# DM1097_Connector.net
KiCad netlist of a schematic drawn in Altium Designer
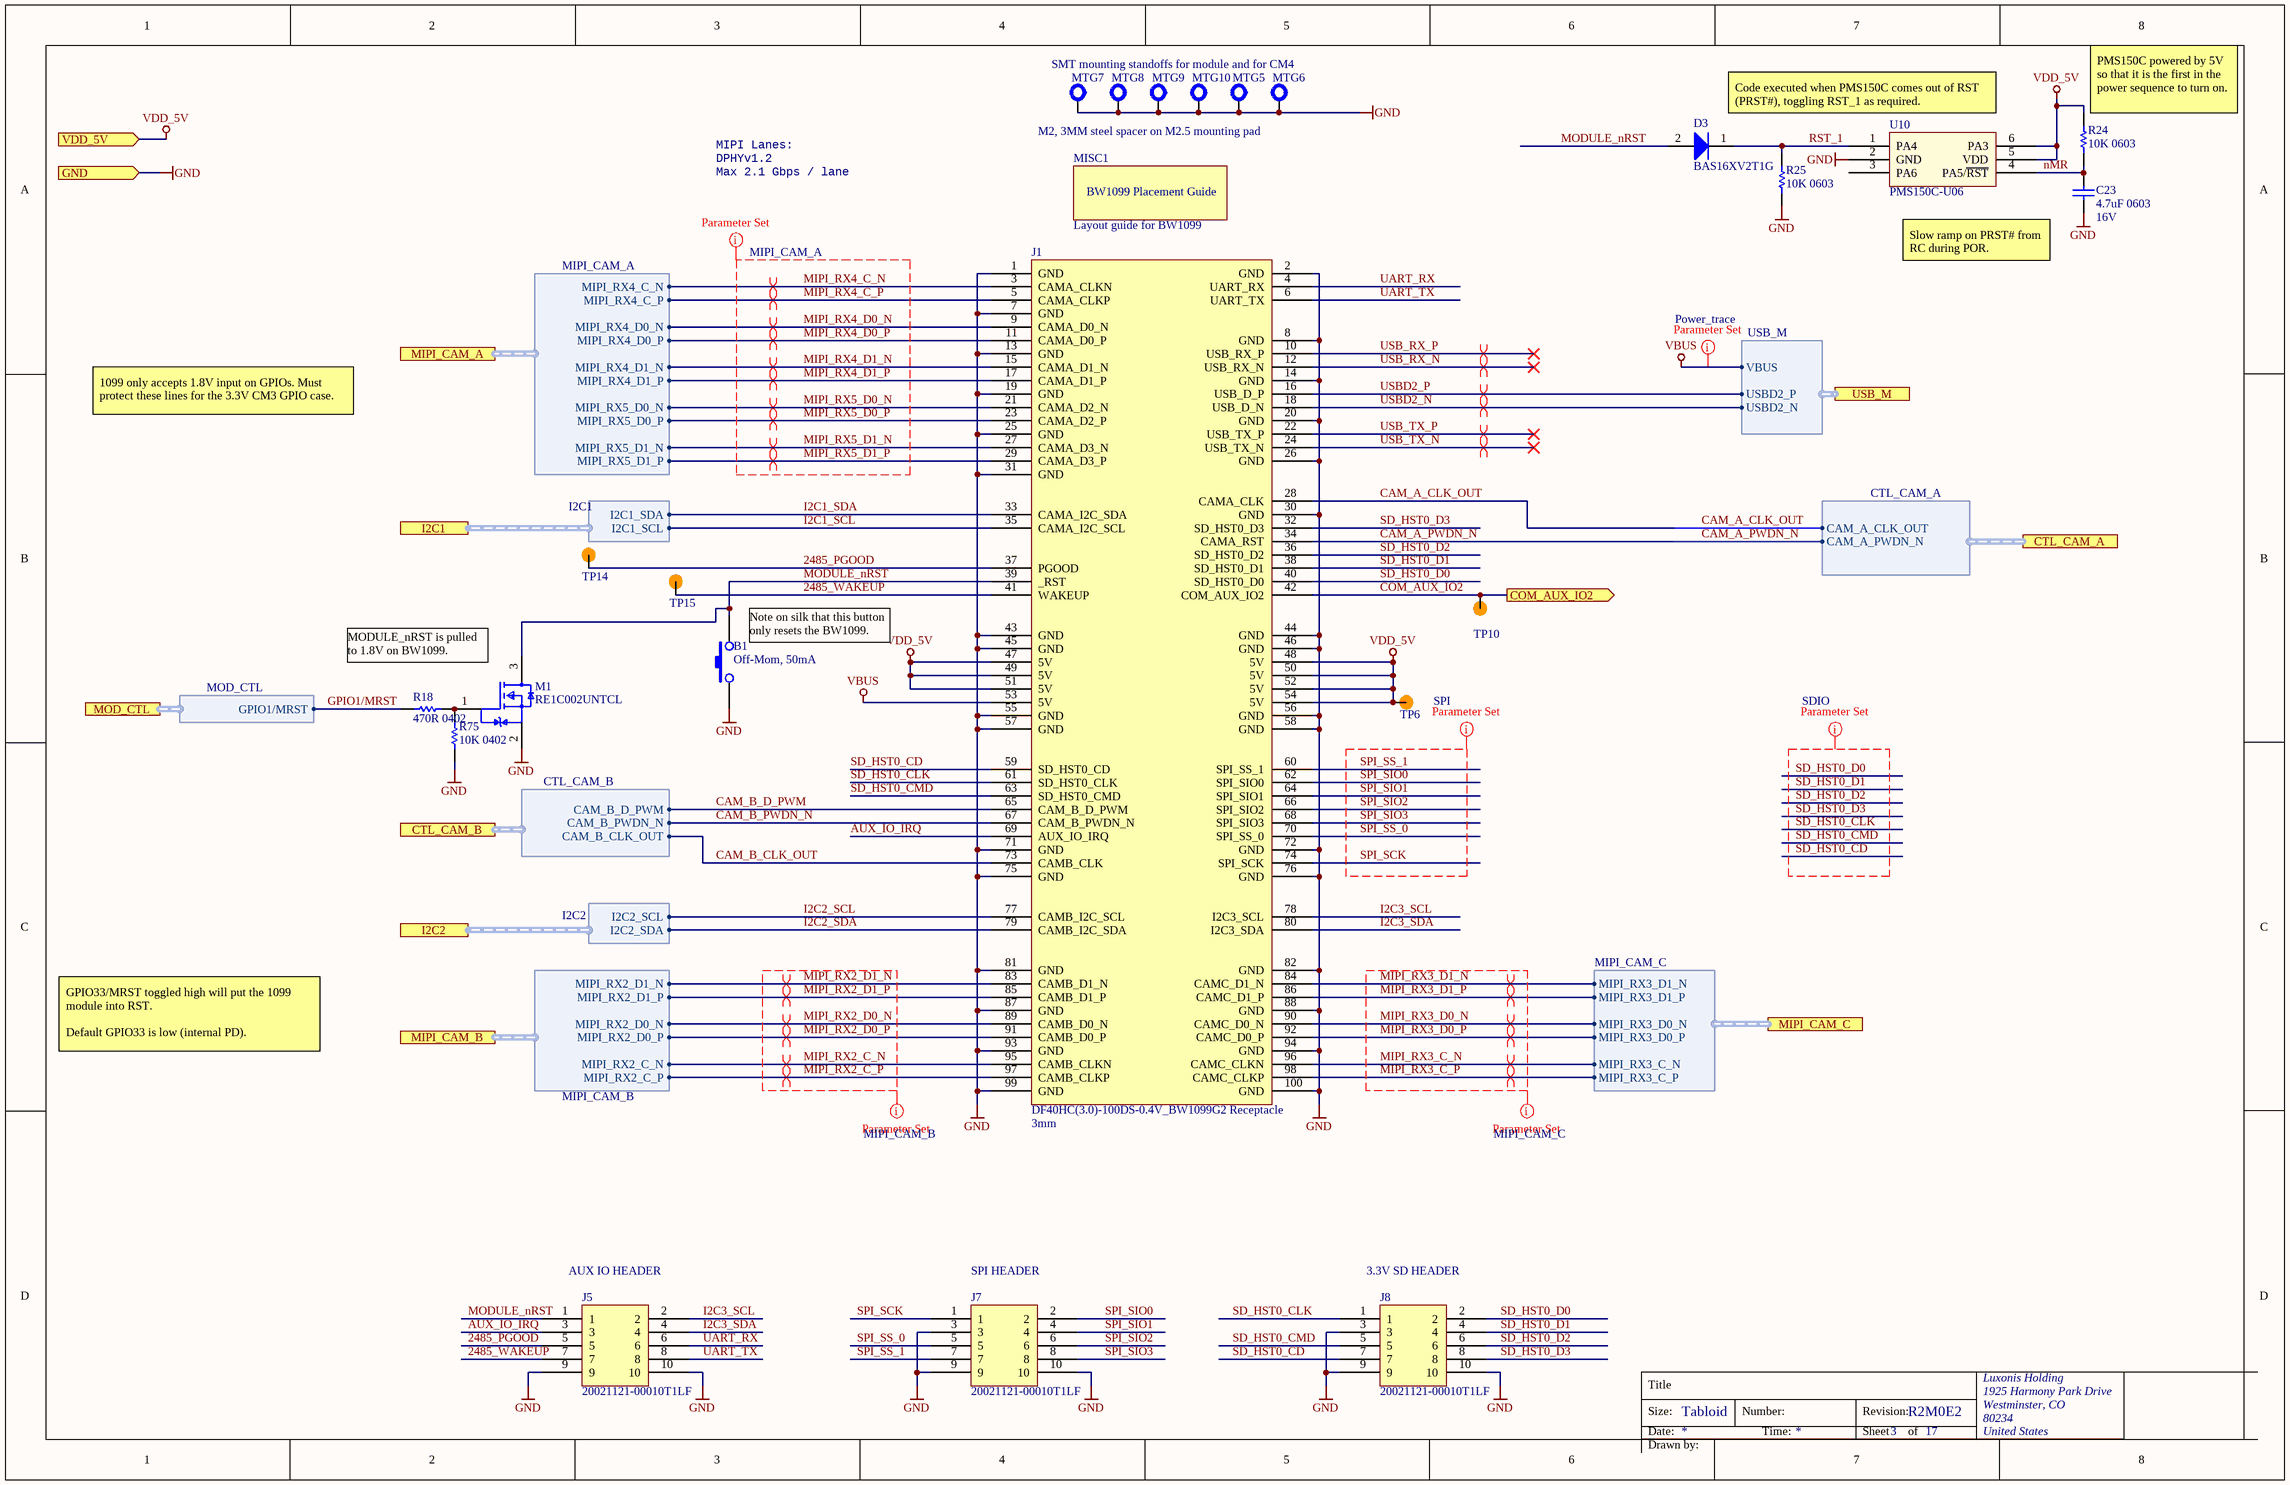
[diagram p0: DM1097_Connector.SchDoc]

(export (version "E")
  (design (tool "Eeschema 10.0.6"))
  (components
    (comp (ref "B1")
      (value "Off-Mom, 50mA")
      (footprint "LuxonisMaster:DTSM-32N-V")
      (description "SWITCH TACTILE SMT 3.5mm * 6mm , brown 160gf")
      (libsource (lib "LuxonisMaster") (part "DTSM-32N-V"))
    )
    (comp (ref "C23")
      (value "4.7uF 0603")
      (footprint "CAP_Altium_Vault_Generic:CAPC0603(1608)100_N")
      (description "CAP CER 4.7UF 16V X5R 0603 10%")
      (fields (field (name "TOLERANCE") "10%") (field (name "VOLTAGE RATING") "16V"))
      (libsource (lib "LuxonisMaster") (part "GRM188R61C475KAAJD"))
    )
    (comp (ref "D3")
      (value "BAS16XV2T1G")
      (footprint "LuxonisMaster:BAS16XV2T1G")
      (description "DIODE GEN PURP 75V 200MA SOD523")
      (libsource (lib "LuxonisMaster") (part "BAS16XV2T1G"))
    )
    (comp (ref "J1")
      (value "DF40HC(3.0)-100DS-0.4V_BW1099G2 Receptacle")
      (footprint "LuxonisMaster:DF40HC-3.0-100DS-0.4V_minpad")
      (description "CONN RCPT 100POS 0.4MM SMD GOLD")
      (fields (field (name "MATED STACKING HEIGHT") "3mm"))
      (libsource (lib "LuxonisMaster") (part "DF40HC(3.0)-100DS-0.4V_BW1099_G2"))
    )
    (comp (ref "J5")
      (value "20021121-00010T1LF")
      (footprint "LuxonisMaster:20021121-00010T1LF")
      (description "CONN HEADER SMD 10POS 1.27MM")
      (libsource (lib "LuxonisMaster") (part "20021121-00010T1LF"))
    )
    (comp (ref "J7")
      (value "20021121-00010T1LF")
      (footprint "LuxonisMaster:20021121-00010T1LF")
      (description "CONN HEADER SMD 10POS 1.27MM")
      (libsource (lib "LuxonisMaster") (part "20021121-00010T1LF"))
    )
    (comp (ref "J8")
      (value "20021121-00010T1LF")
      (footprint "LuxonisMaster:20021121-00010T1LF")
      (description "CONN HEADER SMD 10POS 1.27MM")
      (libsource (lib "LuxonisMaster") (part "20021121-00010T1LF"))
    )
    (comp (ref "M1")
      (value "RE1C002UNTCL")
      (footprint "LuxonisMaster:RE1C002UNTCL")
      (description "MOSFET N-CH 20V 0.2A EMT3")
      (libsource (lib "LuxonisMaster") (part "RE1C002UNTCL"))
    )
    (comp (ref "MISC1")
      (value "Layout guide for BW1099")
      (footprint "BW1099_R3_KTHSNF_Footprint")
      (description "MISC - Use for aligning BW1099 mount")
      (libsource (lib "LuxonisMaster") (part "BW1099_Footprint"))
    )
    (comp (ref "MTG5")
      (value "M2, 3MM steel spacer on M2.5 mounting pad")
      (footprint "LuxonisMaster:9774030243R")
      (description "MP ROUND STANDOFF M2X0.4 STEEL 3MM")
      (libsource (lib "LuxonisMaster") (part "9774030243R"))
    )
    (comp (ref "MTG6")
      (value "M2, 3MM steel spacer on M2.5 mounting pad")
      (footprint "LuxonisMaster:9774030243R")
      (description "MP ROUND STANDOFF M2X0.4 STEEL 3MM")
      (libsource (lib "LuxonisMaster") (part "9774030243R"))
    )
    (comp (ref "MTG7")
      (value "M2, 3MM steel spacer on M2.5 mounting pad")
      (footprint "LuxonisMaster:9774030243R")
      (description "MP ROUND STANDOFF M2X0.4 STEEL 3MM")
      (libsource (lib "LuxonisMaster") (part "9774030243R"))
    )
    (comp (ref "MTG8")
      (value "M2, 3MM steel spacer on M2.5 mounting pad")
      (footprint "LuxonisMaster:9774030243R")
      (description "MP ROUND STANDOFF M2X0.4 STEEL 3MM")
      (libsource (lib "LuxonisMaster") (part "9774030243R"))
    )
    (comp (ref "MTG9")
      (value "M2, 3MM steel spacer on M2.5 mounting pad")
      (footprint "LuxonisMaster:9774030243R")
      (description "MP ROUND STANDOFF M2X0.4 STEEL 3MM")
      (libsource (lib "LuxonisMaster") (part "9774030243R"))
    )
    (comp (ref "MTG10")
      (value "M2, 3MM steel spacer on M2.5 mounting pad")
      (footprint "LuxonisMaster:9774030243R")
      (description "MP ROUND STANDOFF M2X0.4 STEEL 3MM")
      (libsource (lib "LuxonisMaster") (part "9774030243R"))
    )
    (comp (ref "R18")
      (value "470R 0402")
      (footprint "RES_Altium_Vault_Generic:RESC0402(1005)_N")
      (description "RES SMD 470 OHM 1% 1/16W 0402")
      (fields (field (name "TOLERANCE") "1%"))
      (libsource (lib "LuxonisMaster") (part "CRCW0402470RFKED"))
    )
    (comp (ref "R24")
      (value "10K 0603")
      (footprint "RES_Altium_Vault_Generic:RESC0603(1608)_N")
      (description "RES SMD 10K OHM 1% 1/10W 0603")
      (fields (field (name "TOLERANCE") "1%"))
      (libsource (lib "LuxonisMaster") (part "RC0603FR-0710KL"))
    )
    (comp (ref "R25")
      (value "10K 0603")
      (footprint "RES_Altium_Vault_Generic:RESC0603(1608)_N")
      (description "RES SMD 10K OHM 1% 1/10W 0603")
      (fields (field (name "TOLERANCE") "1%"))
      (libsource (lib "LuxonisMaster") (part "RC0603FR-0710KL"))
    )
    (comp (ref "R75")
      (value "10K 0402")
      (footprint "RES_Altium_Vault_Generic:RESC0402(1005)_N")
      (fields (field (name "TOLERANCE") "1%"))
      (libsource (lib "LuxonisMaster") (part "RC0402FR-1310KL"))
    )
    (comp (ref "TP6")
      (value "TP100_200_NS")
      (footprint "LuxonisMaster:TP100_200_NS")
      (libsource (lib "LuxonisMaster") (part "TEST_POINT"))
    )
    (comp (ref "TP10")
      (value "TP100_200_NS")
      (footprint "LuxonisMaster:TP100_200_NS")
      (libsource (lib "LuxonisMaster") (part "TEST_POINT"))
    )
    (comp (ref "TP14")
      (value "TP100_200_NS")
      (footprint "LuxonisMaster:TP100_200_NS")
      (libsource (lib "LuxonisMaster") (part "TEST_POINT"))
    )
    (comp (ref "TP15")
      (value "TP100_200_NS")
      (footprint "LuxonisMaster:TP100_200_NS")
      (libsource (lib "LuxonisMaster") (part "TEST_POINT"))
    )
    (comp (ref "U10")
      (value "PMS150C-U06")
      (footprint "LuxonisMaster:PMS150C-U06")
      (description "Padauk 8bit OTP Type IO Controller - (SOT-23-6)")
      (libsource (lib "LuxonisMaster") (part "PMS150C-U06"))
    )
  )
  (nets
    (net (code "10") (name "/2485_PGOOD") (class "Default")
      (node (ref "J1") (pin "37") (pinfunction "PGOOD_37") (pintype "passive"))
      (node (ref "J5") (pin "5") (pinfunction "5_5") (pintype "passive"))
      (node (ref "TP14") (pin "1") (pintype "passive"))
    )
    (net (code "11") (name "/2485_WAKEUP") (class "Default")
      (node (ref "J1") (pin "41") (pinfunction "WAKEUP_41") (pintype "passive"))
      (node (ref "J5") (pin "7") (pinfunction "7_7") (pintype "passive"))
      (node (ref "TP15") (pin "1") (pintype "passive"))
    )
    (net (code "12") (name "/AUX_IO_IRQ") (class "Default")
      (node (ref "J1") (pin "69") (pinfunction "AUX_IO_IRQ_69") (pintype "passive"))
      (node (ref "J5") (pin "3") (pinfunction "3_3") (pintype "passive"))
    )
    (net (code "13") (name "/CAM_A_CLK_OUT") (class "Default")
      (node (ref "J1") (pin "28") (pinfunction "CAMA_CLK_28") (pintype "passive"))
    )
    (net (code "14") (name "/CAM_A_PWDN_N") (class "Default")
      (node (ref "J1") (pin "34") (pinfunction "CAMA_RST_34") (pintype "passive"))
    )
    (net (code "15") (name "/CAM_B_CLK_OUT") (class "Default")
      (node (ref "J1") (pin "73") (pinfunction "CAMB_CLK_73") (pintype "passive"))
    )
    (net (code "16") (name "/CAM_B_D_PWM") (class "Default")
      (node (ref "J1") (pin "65") (pinfunction "CAM_B_D_PWM_65") (pintype "passive"))
    )
    (net (code "17") (name "/CAM_B_PWDN_N") (class "Default")
      (node (ref "J1") (pin "67") (pinfunction "CAM_B_PWDN_N_67") (pintype "passive"))
    )
    (net (code "18") (name "/COM_AUX_IO2") (class "Default")
      (node (ref "J1") (pin "42") (pinfunction "COM_AUX_IO2_42") (pintype "passive"))
      (node (ref "TP10") (pin "1") (pintype "passive"))
    )
    (net (code "19") (name "/GPIO1{slash}MRST") (class "Default")
      (node (ref "R18") (pin "1") (pinfunction "1_1") (pintype "passive"))
    )
    (net (code "20") (name "/I2C1_SCL") (class "Default")
      (node (ref "J1") (pin "35") (pinfunction "CAMA_I2C_SCL_35") (pintype "passive"))
    )
    (net (code "21") (name "/I2C1_SDA") (class "Default")
      (node (ref "J1") (pin "33") (pinfunction "CAMA_I2C_SDA_33") (pintype "passive"))
    )
    (net (code "22") (name "/I2C2_SCL") (class "Default")
      (node (ref "J1") (pin "77") (pinfunction "CAMB_I2C_SCL_77") (pintype "passive"))
    )
    (net (code "23") (name "/I2C2_SDA") (class "Default")
      (node (ref "J1") (pin "79") (pinfunction "CAMB_I2C_SDA_79") (pintype "passive"))
    )
    (net (code "24") (name "/I2C3_SCL") (class "Default")
      (node (ref "J1") (pin "78") (pinfunction "I2C3_SCL_78") (pintype "passive"))
      (node (ref "J5") (pin "2") (pinfunction "2_2") (pintype "passive"))
    )
    (net (code "25") (name "/I2C3_SDA") (class "Default")
      (node (ref "J1") (pin "80") (pinfunction "I2C3_SDA_80") (pintype "passive"))
      (node (ref "J5") (pin "4") (pinfunction "4_4") (pintype "passive"))
    )
    (net (code "26") (name "/MIPI_RX2_C_N") (class "Default")
      (node (ref "J1") (pin "95") (pinfunction "CAMB_CLKN_95") (pintype "passive"))
    )
    (net (code "27") (name "/MIPI_RX2_C_P") (class "Default")
      (node (ref "J1") (pin "97") (pinfunction "CAMB_CLKP_97") (pintype "passive"))
    )
    (net (code "28") (name "/MIPI_RX2_D0_N") (class "Default")
      (node (ref "J1") (pin "89") (pinfunction "CAMB_D0_N_89") (pintype "passive"))
    )
    (net (code "29") (name "/MIPI_RX2_D0_P") (class "Default")
      (node (ref "J1") (pin "91") (pinfunction "CAMB_D0_P_91") (pintype "passive"))
    )
    (net (code "30") (name "/MIPI_RX2_D1_N") (class "Default")
      (node (ref "J1") (pin "83") (pinfunction "CAMB_D1_N_83") (pintype "passive"))
    )
    (net (code "31") (name "/MIPI_RX2_D1_P") (class "Default")
      (node (ref "J1") (pin "85") (pinfunction "CAMB_D1_P_85") (pintype "passive"))
    )
    (net (code "32") (name "/MIPI_RX3_C_N") (class "Default")
      (node (ref "J1") (pin "96") (pinfunction "CAMC_CLKN_96") (pintype "passive"))
    )
    (net (code "33") (name "/MIPI_RX3_C_P") (class "Default")
      (node (ref "J1") (pin "98") (pinfunction "CAMC_CLKP_98") (pintype "passive"))
    )
    (net (code "34") (name "/MIPI_RX3_D0_N") (class "Default")
      (node (ref "J1") (pin "90") (pinfunction "CAMC_D0_N_90") (pintype "passive"))
    )
    (net (code "35") (name "/MIPI_RX3_D0_P") (class "Default")
      (node (ref "J1") (pin "92") (pinfunction "CAMC_D0_P_92") (pintype "passive"))
    )
    (net (code "36") (name "/MIPI_RX3_D1_N") (class "Default")
      (node (ref "J1") (pin "84") (pinfunction "CAMC_D1_N_84") (pintype "passive"))
    )
    (net (code "37") (name "/MIPI_RX3_D1_P") (class "Default")
      (node (ref "J1") (pin "86") (pinfunction "CAMC_D1_P_86") (pintype "passive"))
    )
    (net (code "38") (name "/MIPI_RX4_C_N") (class "Default")
      (node (ref "J1") (pin "3") (pinfunction "CAMA_CLKN_3") (pintype "passive"))
    )
    (net (code "39") (name "/MIPI_RX4_C_P") (class "Default")
      (node (ref "J1") (pin "5") (pinfunction "CAMA_CLKP_5") (pintype "passive"))
    )
    (net (code "40") (name "/MIPI_RX4_D0_N") (class "Default")
      (node (ref "J1") (pin "9") (pinfunction "CAMA_D0_N_9") (pintype "passive"))
    )
    (net (code "41") (name "/MIPI_RX4_D0_P") (class "Default")
      (node (ref "J1") (pin "11") (pinfunction "CAMA_D0_P_11") (pintype "passive"))
    )
    (net (code "42") (name "/MIPI_RX4_D1_N") (class "Default")
      (node (ref "J1") (pin "15") (pinfunction "CAMA_D1_N_15") (pintype "passive"))
    )
    (net (code "43") (name "/MIPI_RX4_D1_P") (class "Default")
      (node (ref "J1") (pin "17") (pinfunction "CAMA_D1_P_17") (pintype "passive"))
    )
    (net (code "44") (name "/MIPI_RX5_D0_N") (class "Default")
      (node (ref "J1") (pin "21") (pinfunction "CAMA_D2_N_21") (pintype "passive"))
    )
    (net (code "45") (name "/MIPI_RX5_D0_P") (class "Default")
      (node (ref "J1") (pin "23") (pinfunction "CAMA_D2_P_23") (pintype "passive"))
    )
    (net (code "46") (name "/MIPI_RX5_D1_N") (class "Default")
      (node (ref "J1") (pin "27") (pinfunction "CAMA_D3_N_27") (pintype "passive"))
    )
    (net (code "47") (name "/MIPI_RX5_D1_P") (class "Default")
      (node (ref "J1") (pin "29") (pinfunction "CAMA_D3_P_29") (pintype "passive"))
    )
    (net (code "48") (name "/MODULE_nRST") (class "Default")
      (node (ref "B1") (pin "2") (pinfunction "2_2") (pintype "passive"))
      (node (ref "D3") (pin "2") (pinfunction "A_2") (pintype "passive"))
      (node (ref "J1") (pin "39") (pinfunction "_RST_39") (pintype "passive"))
      (node (ref "J5") (pin "1") (pinfunction "1_1") (pintype "passive"))
      (node (ref "M1") (pin "3") (pinfunction "Drain_3") (pintype "passive"))
    )
    (net (code "49") (name "/RST_1") (class "Default")
      (node (ref "D3") (pin "1") (pinfunction "K_1") (pintype "passive"))
      (node (ref "R25") (pin "2") (pinfunction "2_2") (pintype "passive"))
      (node (ref "U10") (pin "1") (pinfunction "PA4_1") (pintype "passive"))
    )
    (net (code "50") (name "/SD_HST0_CD") (class "Default")
      (node (ref "J1") (pin "59") (pinfunction "SD_HST0_CD_59") (pintype "passive"))
      (node (ref "J8") (pin "7") (pinfunction "7_7") (pintype "passive"))
    )
    (net (code "51") (name "/SD_HST0_CLK") (class "Default")
      (node (ref "J1") (pin "61") (pinfunction "SD_HST0_CLK_61") (pintype "passive"))
      (node (ref "J8") (pin "1") (pinfunction "1_1") (pintype "passive"))
    )
    (net (code "52") (name "/SD_HST0_CMD") (class "Default")
      (node (ref "J1") (pin "63") (pinfunction "SD_HST0_CMD_63") (pintype "passive"))
      (node (ref "J8") (pin "5") (pinfunction "5_5") (pintype "passive"))
    )
    (net (code "53") (name "/SD_HST0_D0") (class "Default")
      (node (ref "J1") (pin "40") (pinfunction "SD_HST0_D0_40") (pintype "passive"))
      (node (ref "J8") (pin "2") (pinfunction "2_2") (pintype "passive"))
    )
    (net (code "54") (name "/SD_HST0_D1") (class "Default")
      (node (ref "J1") (pin "38") (pinfunction "SD_HST0_D1_38") (pintype "passive"))
      (node (ref "J8") (pin "4") (pinfunction "4_4") (pintype "passive"))
    )
    (net (code "55") (name "/SD_HST0_D2") (class "Default")
      (node (ref "J1") (pin "36") (pinfunction "SD_HST0_D2_36") (pintype "passive"))
      (node (ref "J8") (pin "6") (pinfunction "6_6") (pintype "passive"))
    )
    (net (code "56") (name "/SD_HST0_D3") (class "Default")
      (node (ref "J1") (pin "32") (pinfunction "SD_HST0_D3_32") (pintype "passive"))
      (node (ref "J8") (pin "8") (pinfunction "8_8") (pintype "passive"))
    )
    (net (code "57") (name "/SPI_SCK") (class "Default")
      (node (ref "J1") (pin "74") (pinfunction "SPI_SCK_74") (pintype "passive"))
      (node (ref "J7") (pin "1") (pinfunction "1_1") (pintype "passive"))
    )
    (net (code "58") (name "/SPI_SIO0") (class "Default")
      (node (ref "J1") (pin "62") (pinfunction "SPI_SIO0_62") (pintype "passive"))
      (node (ref "J7") (pin "2") (pinfunction "2_2") (pintype "passive"))
    )
    (net (code "59") (name "/SPI_SIO1") (class "Default")
      (node (ref "J1") (pin "64") (pinfunction "SPI_SIO1_64") (pintype "passive"))
      (node (ref "J7") (pin "4") (pinfunction "4_4") (pintype "passive"))
    )
    (net (code "60") (name "/SPI_SIO2") (class "Default")
      (node (ref "J1") (pin "66") (pinfunction "SPI_SIO2_66") (pintype "passive"))
      (node (ref "J7") (pin "6") (pinfunction "6_6") (pintype "passive"))
    )
    (net (code "61") (name "/SPI_SIO3") (class "Default")
      (node (ref "J1") (pin "68") (pinfunction "SPI_SIO3_68") (pintype "passive"))
      (node (ref "J7") (pin "8") (pinfunction "8_8") (pintype "passive"))
    )
    (net (code "62") (name "/SPI_SS_0") (class "Default")
      (node (ref "J1") (pin "70") (pinfunction "SPI_SS_0_70") (pintype "passive"))
      (node (ref "J7") (pin "5") (pinfunction "5_5") (pintype "passive"))
    )
    (net (code "63") (name "/SPI_SS_1") (class "Default")
      (node (ref "J1") (pin "60") (pinfunction "SPI_SS_1_60") (pintype "passive"))
      (node (ref "J7") (pin "7") (pinfunction "7_7") (pintype "passive"))
    )
    (net (code "64") (name "/UART_RX") (class "Default")
      (node (ref "J1") (pin "4") (pinfunction "UART_RX_4") (pintype "passive"))
      (node (ref "J5") (pin "6") (pinfunction "6_6") (pintype "passive"))
    )
    (net (code "65") (name "/UART_TX") (class "Default")
      (node (ref "J1") (pin "6") (pinfunction "UART_TX_6") (pintype "passive"))
      (node (ref "J5") (pin "8") (pinfunction "8_8") (pintype "passive"))
    )
    (net (code "66") (name "/USBD2_N") (class "Default")
      (node (ref "J1") (pin "18") (pinfunction "USB_D_N_18") (pintype "passive"))
    )
    (net (code "67") (name "/USBD2_P") (class "Default")
      (node (ref "J1") (pin "16") (pinfunction "USB_D_P_16") (pintype "passive"))
    )
    (net (code "68") (name "/USB_RX_N") (class "Default")
      (node (ref "J1") (pin "12") (pinfunction "USB_RX_N_12") (pintype "passive+no_connect"))
    )
    (net (code "69") (name "/USB_RX_P") (class "Default")
      (node (ref "J1") (pin "10") (pinfunction "USB_RX_P_10") (pintype "passive+no_connect"))
    )
    (net (code "70") (name "/USB_TX_N") (class "Default")
      (node (ref "J1") (pin "24") (pinfunction "USB_TX_N_24") (pintype "passive+no_connect"))
    )
    (net (code "71") (name "/USB_TX_P") (class "Default")
      (node (ref "J1") (pin "22") (pinfunction "USB_TX_P_22") (pintype "passive+no_connect"))
    )
    (net (code "72") (name "/nMR") (class "Default")
      (node (ref "C23") (pin "2") (pinfunction "2_2") (pintype "passive"))
      (node (ref "R24") (pin "1") (pinfunction "1_1") (pintype "passive"))
      (node (ref "U10") (pin "4") (pinfunction "PA5/~{RST}_4") (pintype "passive"))
    )
    (net (code "82") (name "GND") (class "Default")
      (node (ref "B1") (pin "1") (pinfunction "1_1") (pintype "passive"))
      (node (ref "C23") (pin "1") (pinfunction "1_1") (pintype "passive"))
      (node (ref "J1") (pin "1") (pinfunction "GND_1") (pintype "passive"))
      (node (ref "J1") (pin "100") (pinfunction "GND_100") (pintype "passive"))
      (node (ref "J1") (pin "13") (pinfunction "GND_13") (pintype "passive"))
      (node (ref "J1") (pin "14") (pinfunction "GND_14") (pintype "passive"))
      (node (ref "J1") (pin "19") (pinfunction "GND_19") (pintype "passive"))
      (node (ref "J1") (pin "2") (pinfunction "GND_2") (pintype "passive"))
      (node (ref "J1") (pin "20") (pinfunction "GND_20") (pintype "passive"))
      (node (ref "J1") (pin "25") (pinfunction "GND_25") (pintype "passive"))
      (node (ref "J1") (pin "26") (pinfunction "GND_26") (pintype "passive"))
      (node (ref "J1") (pin "30") (pinfunction "GND_30") (pintype "passive"))
      (node (ref "J1") (pin "31") (pinfunction "GND_31") (pintype "passive"))
      (node (ref "J1") (pin "43") (pinfunction "GND_43") (pintype "passive"))
      (node (ref "J1") (pin "44") (pinfunction "GND_44") (pintype "passive"))
      (node (ref "J1") (pin "45") (pinfunction "GND_45") (pintype "passive"))
      (node (ref "J1") (pin "46") (pinfunction "GND_46") (pintype "passive"))
      (node (ref "J1") (pin "55") (pinfunction "GND_55") (pintype "passive"))
      (node (ref "J1") (pin "56") (pinfunction "GND_56") (pintype "passive"))
      (node (ref "J1") (pin "57") (pinfunction "GND_57") (pintype "passive"))
      (node (ref "J1") (pin "58") (pinfunction "GND_58") (pintype "passive"))
      (node (ref "J1") (pin "7") (pinfunction "GND_7") (pintype "passive"))
      (node (ref "J1") (pin "71") (pinfunction "GND_71") (pintype "passive"))
      (node (ref "J1") (pin "72") (pinfunction "GND_72") (pintype "passive"))
      (node (ref "J1") (pin "75") (pinfunction "GND_75") (pintype "passive"))
      (node (ref "J1") (pin "76") (pinfunction "GND_76") (pintype "passive"))
      (node (ref "J1") (pin "8") (pinfunction "GND_8") (pintype "passive"))
      (node (ref "J1") (pin "81") (pinfunction "GND_81") (pintype "passive"))
      (node (ref "J1") (pin "82") (pinfunction "GND_82") (pintype "passive"))
      (node (ref "J1") (pin "87") (pinfunction "GND_87") (pintype "passive"))
      (node (ref "J1") (pin "88") (pinfunction "GND_88") (pintype "passive"))
      (node (ref "J1") (pin "93") (pinfunction "GND_93") (pintype "passive"))
      (node (ref "J1") (pin "94") (pinfunction "GND_94") (pintype "passive"))
      (node (ref "J1") (pin "99") (pinfunction "GND_99") (pintype "passive"))
      (node (ref "J5") (pin "10") (pinfunction "10_10") (pintype "passive"))
      (node (ref "J5") (pin "9") (pinfunction "9_9") (pintype "passive"))
      (node (ref "J7") (pin "10") (pinfunction "10_10") (pintype "passive"))
      (node (ref "J7") (pin "3") (pinfunction "3_3") (pintype "passive"))
      (node (ref "J7") (pin "9") (pinfunction "9_9") (pintype "passive"))
      (node (ref "J8") (pin "10") (pinfunction "10_10") (pintype "passive"))
      (node (ref "J8") (pin "3") (pinfunction "3_3") (pintype "passive"))
      (node (ref "J8") (pin "9") (pinfunction "9_9") (pintype "passive"))
      (node (ref "M1") (pin "2") (pinfunction "Source_2") (pintype "passive"))
      (node (ref "MTG10") (pin "1") (pintype "passive"))
      (node (ref "MTG5") (pin "1") (pintype "passive"))
      (node (ref "MTG6") (pin "1") (pintype "passive"))
      (node (ref "MTG7") (pin "1") (pintype "passive"))
      (node (ref "MTG8") (pin "1") (pintype "passive"))
      (node (ref "MTG9") (pin "1") (pintype "passive"))
      (node (ref "R25") (pin "1") (pinfunction "1_1") (pintype "passive"))
      (node (ref "R75") (pin "1") (pinfunction "1_1") (pintype "passive"))
      (node (ref "U10") (pin "2") (pinfunction "GND_2") (pintype "passive"))
    )
    (net (code "83") (name "Net-(M1-Gate)") (class "Default")
      (node (ref "M1") (pin "1") (pinfunction "Gate_1") (pintype "passive"))
      (node (ref "R18") (pin "2") (pinfunction "2_2") (pintype "passive"))
      (node (ref "R75") (pin "2") (pinfunction "2_2") (pintype "passive"))
    )
    (net (code "84") (name "VBUS") (class "Default")
      (node (ref "J1") (pin "53") (pinfunction "5V_53") (pintype "passive"))
    )
    (net (code "85") (name "VDD_5V") (class "Default")
      (node (ref "J1") (pin "47") (pinfunction "5V_47") (pintype "passive"))
      (node (ref "J1") (pin "48") (pinfunction "5V_48") (pintype "passive"))
      (node (ref "J1") (pin "49") (pinfunction "5V_49") (pintype "passive"))
      (node (ref "J1") (pin "50") (pinfunction "5V_50") (pintype "passive"))
      (node (ref "J1") (pin "51") (pinfunction "5V_51") (pintype "passive"))
      (node (ref "J1") (pin "52") (pinfunction "5V_52") (pintype "passive"))
      (node (ref "J1") (pin "54") (pinfunction "5V_54") (pintype "passive"))
      (node (ref "R24") (pin "2") (pinfunction "2_2") (pintype "passive"))
      (node (ref "TP6") (pin "1") (pintype "passive"))
      (node (ref "U10") (pin "5") (pinfunction "VDD_5") (pintype "passive"))
      (node (ref "U10") (pin "6") (pinfunction "PA3_6") (pintype "passive"))
    )
    (net (code "86") (name "unconnected-(U10-PA6-Pad3)") (class "Default")
      (node (ref "U10") (pin "3") (pinfunction "PA6_3") (pintype "passive"))
    )
  )
)
